# FM_MODULE.net
KiCad netlist of a schematic drawn in Altium Designer
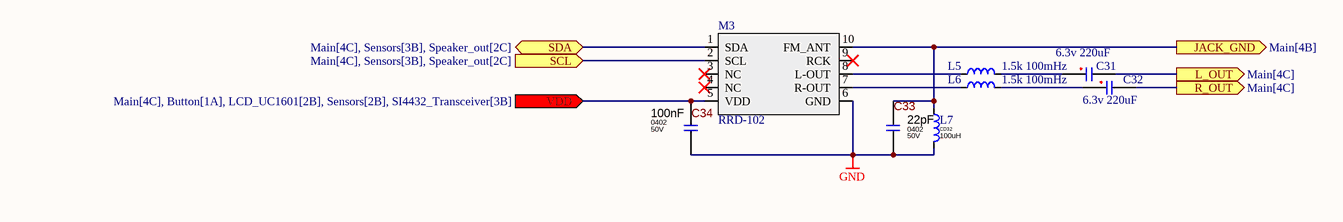
[diagram p0: FM_MODULE.SchDoc]

(export (version "E")
  (design (tool "Eeschema 10.0.6"))
  (components
    (comp (ref "C31")
      (value "6.3v 220uF")
      (footprint "Tantalum TYPE-B")
      (libsource (lib "Capacitors") (part "Tantalum_TYPE-B"))
    )
    (comp (ref "C32")
      (value "6.3v 220uF")
      (footprint "Tantalum TYPE-B")
      (libsource (lib "Capacitors") (part "Tantalum_TYPE-B"))
    )
    (comp (ref "C33")
      (value "22pF")
      (footprint "Cap_0402")
      (description "22pF 50V  ±25% 0402 Ceramic Capacitor")
      (fields
        (field (name "TOLERANCE") "±25%")
        (field (name "PACKAGE") "0402")
        (field (name "VOLTAGE") "50V")
      )
      (libsource (lib "Capacitors") (part "Cap_0402_22pF"))
    )
    (comp (ref "C34")
      (value "100nF")
      (footprint "Cap_0402")
      (description "100nF 50V  ±25% 0402 Ceramic Capacitor")
      (fields
        (field (name "TOLERANCE") "±25%")
        (field (name "PACKAGE") "0402")
        (field (name "VOLTAGE") "50V")
      )
      (libsource (lib "Capacitors") (part "Cap_0402_100nF"))
    )
    (comp (ref "L5") (value "1.5k 100mHz") (footprint "Cap_0805") (libsource (lib "Inductors") (part "0805")))
    (comp (ref "L6") (value "1.5k 100mHz") (footprint "Cap_0805") (libsource (lib "Inductors") (part "0805")))
    (comp (ref "L7")
      (value "100uH")
      (footprint "Footprints:CD32")
      (description "2.2uH")
      (fields (field (name "SIZE") "CD32") (field (name "Comment") "CD32"))
      (libsource (lib "Inductors") (part "CD32"))
    )
    (comp (ref "M3")
      (value "RRD-102")
      (footprint "RRD-102")
      (libsource (lib "Module") (part "RRD-102(RDA5807M)"))
    )
  )
  (nets
    (net (code "1") (name "/JACK_GND") (class "Default")
      (node (ref "C33") (pin "1") (pinfunction "1_1") (pintype "passive"))
      (node (ref "L7") (pin "1") (pinfunction "1_1") (pintype "passive"))
      (node (ref "M3") (pin "10") (pinfunction "FM_ANT_10") (pintype "passive"))
    )
    (net (code "2") (name "/L_OUT") (class "Default")
      (node (ref "C31") (pin "2") (pinfunction "2_2") (pintype "passive"))
    )
    (net (code "3") (name "/R_OUT") (class "Default")
      (node (ref "C32") (pin "2") (pinfunction "2_2") (pintype "passive"))
    )
    (net (code "4") (name "/SCL") (class "Default")
      (node (ref "M3") (pin "2") (pinfunction "SCL_2") (pintype "passive"))
    )
    (net (code "5") (name "/SDA") (class "Default")
      (node (ref "M3") (pin "1") (pinfunction "SDA_1") (pintype "passive"))
    )
    (net (code "6") (name "/VDD") (class "Default")
      (node (ref "C34") (pin "1") (pinfunction "1_1") (pintype "passive"))
      (node (ref "M3") (pin "5") (pinfunction "VDD_5") (pintype "passive"))
    )
    (net (code "7") (name "GND") (class "Default")
      (node (ref "C33") (pin "2") (pinfunction "2_2") (pintype "passive"))
      (node (ref "C34") (pin "2") (pinfunction "2_2") (pintype "passive"))
      (node (ref "L7") (pin "2") (pinfunction "2_2") (pintype "passive"))
      (node (ref "M3") (pin "6") (pinfunction "GND_6") (pintype "passive"))
    )
    (net (code "8") (name "Net-(C31-Pad1)") (class "Default")
      (node (ref "C31") (pin "1") (pinfunction "1_1") (pintype "passive"))
      (node (ref "L5") (pin "2") (pinfunction "2_2") (pintype "passive"))
    )
    (net (code "9") (name "Net-(C32-Pad1)") (class "Default")
      (node (ref "C32") (pin "1") (pinfunction "1_1") (pintype "passive"))
      (node (ref "L6") (pin "2") (pinfunction "2_2") (pintype "passive"))
    )
    (net (code "10") (name "Net-(M3-L-OUT)") (class "Default")
      (node (ref "L5") (pin "1") (pinfunction "1_1") (pintype "passive"))
      (node (ref "M3") (pin "8") (pinfunction "L-OUT_8") (pintype "passive"))
    )
    (net (code "11") (name "Net-(M3-R-OUT)") (class "Default")
      (node (ref "L6") (pin "1") (pinfunction "1_1") (pintype "passive"))
      (node (ref "M3") (pin "7") (pinfunction "R-OUT_7") (pintype "passive"))
    )
    (net (code "12") (name "unconnected-(M3-NC-Pad3)") (class "Default")
      (node (ref "M3") (pin "3") (pinfunction "NC_3") (pintype "passive+no_connect"))
    )
    (net (code "13") (name "unconnected-(M3-NC-Pad4)") (class "Default")
      (node (ref "M3") (pin "4") (pinfunction "NC_4") (pintype "passive+no_connect"))
    )
    (net (code "14") (name "unconnected-(M3-RCK-Pad9)") (class "Default")
      (node (ref "M3") (pin "9") (pinfunction "RCK_9") (pintype "passive+no_connect"))
    )
  )
)
